# 17_-SP2_BUCKs_GPU_LOG_CPU-B.net
KiCad netlist of a schematic drawn in Altium Designer
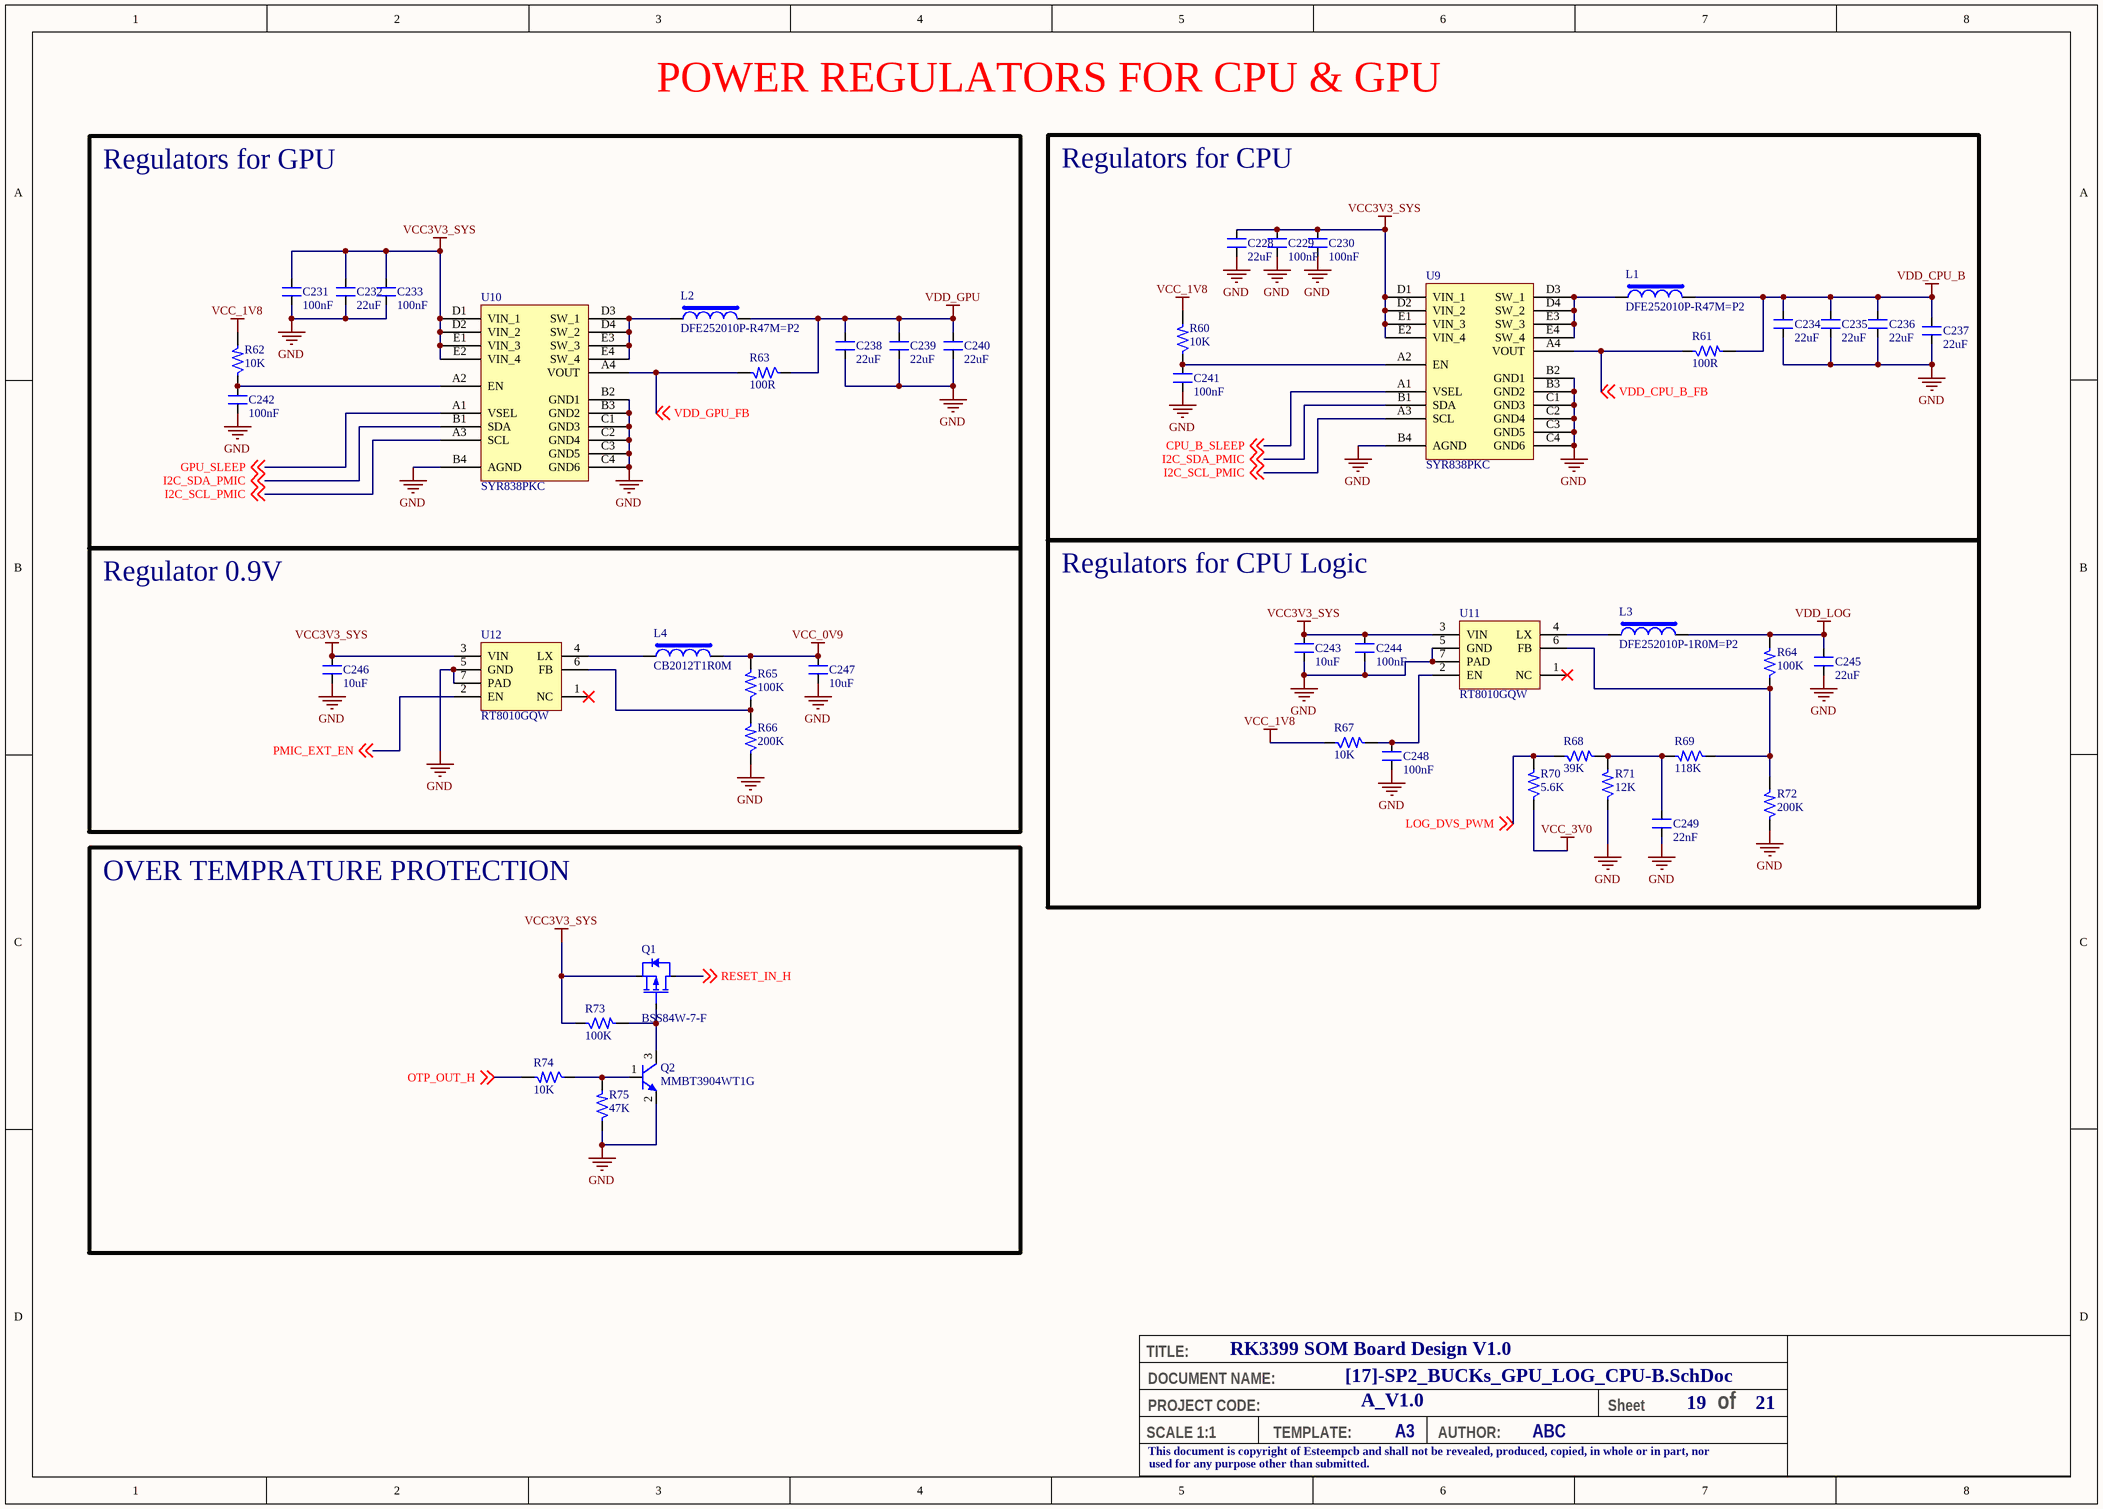
[diagram p0: [17]-SP2_BUCKs_GPU_LOG_CPU-B.SchDoc]

(export (version "E")
  (design (tool "Eeschema 10.0.6"))
  (components
    (comp (ref "C228")
      (value "22uF")
      (footprint "CAP_0603")
      (description "22µF ±20% 10V Ceramic Capacitor X5R 0603 (1608 Metric)")
      (fields
        (field (name "MANUFACTURER") "Murata Electronics")
        (field (name "MANUFACTURER PART NUMBER") "GRM188R61A226ME15D")
      )
      (libsource (lib "RK3399 _Module_Schlib") (part "CAP_22uF-10V-20%-0603"))
    )
    (comp (ref "C229")
      (value "100nF")
      (footprint "CAP_0402")
      (description "0.1µF ±10% 25V Ceramic Capacitor X7R 0402 (1005 Metric)")
      (fields
        (field (name "MANUFACTURER") "Walsin Technology Corporation")
        (field (name "MANUFACTURER PART NUMBER") "0402B104K250CT")
      )
      (libsource (lib "RK3399 _Module_Schlib") (part "CAP_100nF-25V-10%-0402"))
    )
    (comp (ref "C230")
      (value "100nF")
      (footprint "CAP_0402")
      (description "0.1µF ±10% 25V Ceramic Capacitor X7R 0402 (1005 Metric)")
      (fields
        (field (name "MANUFACTURER") "Walsin Technology Corporation")
        (field (name "MANUFACTURER PART NUMBER") "0402B104K250CT")
      )
      (libsource (lib "RK3399 _Module_Schlib") (part "CAP_100nF-25V-10%-0402"))
    )
    (comp (ref "C231")
      (value "100nF")
      (footprint "CAP_0402")
      (description "0.1µF ±10% 25V Ceramic Capacitor X7R 0402 (1005 Metric)")
      (fields
        (field (name "MANUFACTURER") "Walsin Technology Corporation")
        (field (name "MANUFACTURER PART NUMBER") "0402B104K250CT")
      )
      (libsource (lib "RK3399 _Module_Schlib") (part "CAP_100nF-25V-10%-0402"))
    )
    (comp (ref "C232")
      (value "22uF")
      (footprint "CAP_0603")
      (description "22µF ±20% 10V Ceramic Capacitor X5R 0603 (1608 Metric)")
      (fields
        (field (name "MANUFACTURER") "Murata Electronics")
        (field (name "MANUFACTURER PART NUMBER") "GRM188R61A226ME15D")
      )
      (libsource (lib "RK3399 _Module_Schlib") (part "CAP_22uF-10V-20%-0603"))
    )
    (comp (ref "C233")
      (value "100nF")
      (footprint "CAP_0402")
      (description "0.1µF ±10% 25V Ceramic Capacitor X7R 0402 (1005 Metric)")
      (fields
        (field (name "MANUFACTURER") "Walsin Technology Corporation")
        (field (name "MANUFACTURER PART NUMBER") "0402B104K250CT")
      )
      (libsource (lib "RK3399 _Module_Schlib") (part "CAP_100nF-25V-10%-0402"))
    )
    (comp (ref "C234")
      (value "22uF")
      (footprint "CAP_0603")
      (description "22µF ±20% 10V Ceramic Capacitor X5R 0603 (1608 Metric)")
      (fields
        (field (name "MANUFACTURER") "Murata Electronics")
        (field (name "MANUFACTURER PART NUMBER") "GRM188R61A226ME15D")
      )
      (libsource (lib "RK3399 _Module_Schlib") (part "CAP_22uF-10V-20%-0603"))
    )
    (comp (ref "C235")
      (value "22uF")
      (footprint "CAP_0603")
      (description "22µF ±20% 10V Ceramic Capacitor X5R 0603 (1608 Metric)")
      (fields
        (field (name "MANUFACTURER") "Murata Electronics")
        (field (name "MANUFACTURER PART NUMBER") "GRM188R61A226ME15D")
      )
      (libsource (lib "RK3399 _Module_Schlib") (part "CAP_22uF-10V-20%-0603"))
    )
    (comp (ref "C236")
      (value "22uF")
      (footprint "CAP_0603")
      (description "22µF ±20% 10V Ceramic Capacitor X5R 0603 (1608 Metric)")
      (fields
        (field (name "MANUFACTURER") "Murata Electronics")
        (field (name "MANUFACTURER PART NUMBER") "GRM188R61A226ME15D")
      )
      (libsource (lib "RK3399 _Module_Schlib") (part "CAP_22uF-10V-20%-0603"))
    )
    (comp (ref "C237")
      (value "22uF")
      (footprint "CAP_0603")
      (description "22µF ±20% 10V Ceramic Capacitor X5R 0603 (1608 Metric)")
      (fields
        (field (name "MANUFACTURER") "Murata Electronics")
        (field (name "MANUFACTURER PART NUMBER") "GRM188R61A226ME15D")
      )
      (libsource (lib "RK3399 _Module_Schlib") (part "CAP_22uF-10V-20%-0603"))
    )
    (comp (ref "C238")
      (value "22uF")
      (footprint "CAP_0603")
      (description "22µF ±20% 10V Ceramic Capacitor X5R 0603 (1608 Metric)")
      (fields
        (field (name "MANUFACTURER") "Murata Electronics")
        (field (name "MANUFACTURER PART NUMBER") "GRM188R61A226ME15D")
      )
      (libsource (lib "RK3399 _Module_Schlib") (part "CAP_22uF-10V-20%-0603"))
    )
    (comp (ref "C239")
      (value "22uF")
      (footprint "CAP_0603")
      (description "22µF ±20% 10V Ceramic Capacitor X5R 0603 (1608 Metric)")
      (fields
        (field (name "MANUFACTURER") "Murata Electronics")
        (field (name "MANUFACTURER PART NUMBER") "GRM188R61A226ME15D")
      )
      (libsource (lib "RK3399 _Module_Schlib") (part "CAP_22uF-10V-20%-0603"))
    )
    (comp (ref "C240")
      (value "22uF")
      (footprint "CAP_0603")
      (description "22µF ±20% 10V Ceramic Capacitor X5R 0603 (1608 Metric)")
      (fields
        (field (name "MANUFACTURER") "Murata Electronics")
        (field (name "MANUFACTURER PART NUMBER") "GRM188R61A226ME15D")
      )
      (libsource (lib "RK3399 _Module_Schlib") (part "CAP_22uF-10V-20%-0603"))
    )
    (comp (ref "C241")
      (value "100nF")
      (footprint "CAP_0402")
      (description "0.1µF ±10% 25V Ceramic Capacitor X7R 0402 (1005 Metric)")
      (fields
        (field (name "MANUFACTURER") "Walsin Technology Corporation")
        (field (name "MANUFACTURER PART NUMBER") "0402B104K250CT")
      )
      (libsource (lib "RK3399 _Module_Schlib") (part "CAP_100nF-25V-10%-0402"))
    )
    (comp (ref "C242")
      (value "100nF")
      (footprint "CAP_0402")
      (description "0.1µF ±10% 25V Ceramic Capacitor X7R 0402 (1005 Metric)")
      (fields
        (field (name "MANUFACTURER") "Walsin Technology Corporation")
        (field (name "MANUFACTURER PART NUMBER") "0402B104K250CT")
      )
      (libsource (lib "RK3399 _Module_Schlib") (part "CAP_100nF-25V-10%-0402"))
    )
    (comp (ref "C243")
      (value "10uF")
      (footprint "CAP_0402")
      (description "10µF ±20% 10V Ceramic Capacitor X5R 0402 (1005 Metric)")
      (fields
        (field (name "MANUFACTURER PART NUMBER") "CL05A106MP5NUNC")
        (field (name "MANUFACTURER") "Samsung Electro-Mechanics")
      )
      (libsource (lib "RK3399 _Module_Schlib") (part "CAP_10uF-10V-20%-0402"))
    )
    (comp (ref "C244")
      (value "100nF")
      (footprint "CAP_0402")
      (description "0.1µF ±10% 25V Ceramic Capacitor X7R 0402 (1005 Metric)")
      (fields
        (field (name "MANUFACTURER") "Walsin Technology Corporation")
        (field (name "MANUFACTURER PART NUMBER") "0402B104K250CT")
      )
      (libsource (lib "RK3399 _Module_Schlib") (part "CAP_100nF-25V-10%-0402"))
    )
    (comp (ref "C245")
      (value "22uF")
      (footprint "CAP_0603")
      (description "22µF ±20% 10V Ceramic Capacitor X5R 0603 (1608 Metric)")
      (fields
        (field (name "MANUFACTURER") "Murata Electronics")
        (field (name "MANUFACTURER PART NUMBER") "GRM188R61A226ME15D")
      )
      (libsource (lib "RK3399 _Module_Schlib") (part "CAP_22uF-10V-20%-0603"))
    )
    (comp (ref "C246")
      (value "10uF")
      (footprint "CAP_0402")
      (description "10µF ±20% 10V Ceramic Capacitor X5R 0402 (1005 Metric)")
      (fields
        (field (name "MANUFACTURER PART NUMBER") "CL05A106MP5NUNC")
        (field (name "MANUFACTURER") "Samsung Electro-Mechanics")
      )
      (libsource (lib "RK3399 _Module_Schlib") (part "CAP_10uF-10V-20%-0402"))
    )
    (comp (ref "C247")
      (value "10uF")
      (footprint "CAP_0402")
      (description "10µF ±20% 10V Ceramic Capacitor X5R 0402 (1005 Metric)")
      (fields
        (field (name "MANUFACTURER PART NUMBER") "CL05A106MP5NUNC")
        (field (name "MANUFACTURER") "Samsung Electro-Mechanics")
      )
      (libsource (lib "RK3399 _Module_Schlib") (part "CAP_10uF-10V-20%-0402"))
    )
    (comp (ref "C248")
      (value "100nF")
      (footprint "CAP_0402")
      (description "0.1µF ±10% 25V Ceramic Capacitor X7R 0402 (1005 Metric)")
      (fields
        (field (name "MANUFACTURER") "Walsin Technology Corporation")
        (field (name "MANUFACTURER PART NUMBER") "0402B104K250CT")
      )
      (libsource (lib "RK3399 _Module_Schlib") (part "CAP_100nF-25V-10%-0402"))
    )
    (comp (ref "C249")
      (value "22nF")
      (footprint "CAP_0402")
      (description "0.022µF ±10% 10V Ceramic Capacitor X7R 0402 (1005 Metric)")
      (fields
        (field (name "MANUFACTURER") "Samsung Electro-Mechanics")
        (field (name "MANUFACTURER PART NUMBER") "CL05B223KP5NNNC")
      )
      (libsource (lib "RK3399 _Module_Schlib") (part "CAP_22nF-10V-10%-0402"))
    )
    (comp (ref "L1")
      (value "DFE252010P-R47M=P2")
      (footprint "IND_1008")
      (description "470nH Shielded Wirewound Inductor 5A 35mOhm Max 1008 (2520 Metric)")
      (fields (field (name "MANUFACTURER") "Murata Electronics"))
      (libsource (lib "RK3399 _Module_Schlib") (part "IND_470nH-5A-20%-1008"))
    )
    (comp (ref "L2")
      (value "DFE252010P-R47M=P2")
      (footprint "IND_1008")
      (description "470nH Shielded Wirewound Inductor 5A 35mOhm Max 1008 (2520 Metric)")
      (fields (field (name "MANUFACTURER") "Murata Electronics"))
      (libsource (lib "RK3399 _Module_Schlib") (part "IND_470nH-5A-20%-1008"))
    )
    (comp (ref "L3")
      (value "DFE252010P-1R0M=P2")
      (footprint "IND_1008")
      (description "1µH Shielded Wirewound Inductor 3.8A 54mOhm Max 1008 (2520 Metric)")
      (fields (field (name "MANUFACTURER") "Murata Electronics"))
      (libsource (lib "RK3399 _Module_Schlib") (part "IND_1uH-3.8A-20%-1008"))
    )
    (comp (ref "L4")
      (value "CB2012T1R0M")
      (footprint "IND_0805")
      (description "1uH ±20% 500mA 150mΩ 0805 Inductors (SMD) RoHS")
      (fields (field (name "MANUFACTURER") "Taiyo Yuden"))
      (libsource (lib "RK3399 _Module_Schlib") (part "IND_1uF-0.5A-20%-0805"))
    )
    (comp (ref "Q1")
      (value "BSS84W-7-F")
      (footprint "SOT-323-3")
      (description "P-Channel 50V 130mA (Ta) 200mW (Ta) Surface Mount SOT-323")
      (fields (field (name "MANUFACTURER") "Diodes Incorporated"))
      (libsource (lib "RK3399 _Module_Schlib") (part "MOSFET-P_50V-130mA-SOT-323"))
    )
    (comp (ref "Q2")
      (value "MMBT3904WT1G")
      (footprint "SOT-323-3")
      (description "Bipolar Transistors - BJT 200mA 60V NPN")
      (fields (field (name "MANUFACTURER") "ON Semiconductor"))
      (libsource (lib "RK3399 _Module_Schlib") (part "TRNS-NPN_60V-0.2A-SOT323"))
    )
    (comp (ref "R60")
      (value "10K")
      (footprint "RES_0402")
      (description "10 kOhms ±1% 0.1W, 1/10W Chip Resistor 0402 (1005 Metric) Anti-Sulfur Thin Film")
      (fields
        (field (name "MANUFACTURER") "Vishay Beyschlag/Draloric/BC Components")
        (field (name "MANUFACTURER PART NUMBER") "MCS04020C1002FE000")
      )
      (libsource (lib "RK3399 _Module_Schlib") (part "RES_10K-0.1W-1%-0402"))
    )
    (comp (ref "R61")
      (value "100R")
      (footprint "RES_0402")
      (fields
        (field (name "MANUFACTURER") "KOA Speer Electronics, Inc.")
        (field (name "MANUFACTURER PART NUMBER") "RK73H1ETTP1000F")
      )
      (libsource (lib "RK3399 _Module_Schlib") (part "RES_100R-0.1W-1%-0402"))
    )
    (comp (ref "R62")
      (value "10K")
      (footprint "RES_0402")
      (description "10 kOhms ±1% 0.1W, 1/10W Chip Resistor 0402 (1005 Metric) Anti-Sulfur Thin Film")
      (fields
        (field (name "MANUFACTURER") "Vishay Beyschlag/Draloric/BC Components")
        (field (name "MANUFACTURER PART NUMBER") "MCS04020C1002FE000")
      )
      (libsource (lib "RK3399 _Module_Schlib") (part "RES_10K-0.1W-1%-0402"))
    )
    (comp (ref "R63")
      (value "100R")
      (footprint "RES_0402")
      (fields
        (field (name "MANUFACTURER") "KOA Speer Electronics, Inc.")
        (field (name "MANUFACTURER PART NUMBER") "RK73H1ETTP1000F")
      )
      (libsource (lib "RK3399 _Module_Schlib") (part "RES_100R-0.1W-1%-0402"))
    )
    (comp (ref "R64")
      (value "100K")
      (footprint "RES_0402")
      (description "100 kOhms ±1% 0.1W, 1/10W Chip Resistor 0402 (1005 Metric) Anti-Sulfur Thin Film")
      (fields
        (field (name "MANUFACTURER") "Vishay Beyschlag/Draloric/BC Components")
        (field (name "MANUFACTURER PART NUMBER") "MCS04020C1003FE000")
      )
      (libsource (lib "RK3399 _Module_Schlib") (part "RES_100K-0.1W-1%-0402"))
    )
    (comp (ref "R65")
      (value "100K")
      (footprint "RES_0402")
      (description "100 kOhms ±1% 0.1W, 1/10W Chip Resistor 0402 (1005 Metric) Anti-Sulfur Thin Film")
      (fields
        (field (name "MANUFACTURER") "Vishay Beyschlag/Draloric/BC Components")
        (field (name "MANUFACTURER PART NUMBER") "MCS04020C1003FE000")
      )
      (libsource (lib "RK3399 _Module_Schlib") (part "RES_100K-0.1W-1%-0402"))
    )
    (comp (ref "R66")
      (value "200K")
      (footprint "RES_0402")
      (description "200 kOhms ±1% 0.1W, 1/10W Chip Resistor 0402 (1005 Metric) Automotive AEC-Q200 Thick Film")
      (fields
        (field (name "MANUFACTURER") "Panasonic Electronic Components")
        (field (name "MANUFACTURER PART NUMBER") "ERJ-2RKF2003X")
      )
      (libsource (lib "RK3399 _Module_Schlib") (part "RES_200K-0.1W-1%-0402"))
    )
    (comp (ref "R67")
      (value "10K")
      (footprint "RES_0402")
      (description "10 kOhms ±1% 0.1W, 1/10W Chip Resistor 0402 (1005 Metric) Anti-Sulfur Thin Film")
      (fields
        (field (name "MANUFACTURER") "Vishay Beyschlag/Draloric/BC Components")
        (field (name "MANUFACTURER PART NUMBER") "MCS04020C1002FE000")
      )
      (libsource (lib "RK3399 _Module_Schlib") (part "RES_10K-0.1W-1%-0402"))
    )
    (comp (ref "R68")
      (value "39K")
      (footprint "RES_0402")
      (fields
        (field (name "MANUFACTURER") "KOA Speer Electronics, Inc.")
        (field (name "MANUFACTURER PART NUMBER") "RK73H1ETTP3902F")
      )
      (libsource (lib "RK3399 _Module_Schlib") (part "RES_39K-0.1W-1%-0402"))
    )
    (comp (ref "R69")
      (value "118K")
      (footprint "RES_0402")
      (fields
        (field (name "MANUFACTURER") "KOA Speer Electronics, Inc.")
        (field (name "MANUAFCTURER PART NUMBER") "RK73H1ETTP1183F")
      )
      (libsource (lib "RK3399 _Module_Schlib") (part "RES_118K-0.1W-1%-0402"))
    )
    (comp (ref "R70")
      (value "5.6K")
      (footprint "RES_0402")
      (fields
        (field (name "MANUFACTURER") "KOA Speer Electronics, Inc.")
        (field (name "MANUFACTURER PART NUMBER") "RK73H1ETTP5601F")
      )
      (libsource (lib "RK3399 _Module_Schlib") (part "RES_5.6K-0.1W-1%-0402"))
    )
    (comp (ref "R71")
      (value "12K")
      (footprint "RES_0402")
      (description "12 kOhms ±1% 0.1W, 1/10W Chip Resistor 0402 (1005 Metric) Anti-Sulfur Thin Film")
      (fields
        (field (name "MANUFACTURER") "Vishay Beyschlag/Draloric/BC Components")
        (field (name "MANUFACTURER PART NUMBER") "MCS04020C1202FE000")
      )
      (libsource (lib "RK3399 _Module_Schlib") (part "RES_12K-0.1W-1%-0402"))
    )
    (comp (ref "R72")
      (value "200K")
      (footprint "RES_0402")
      (description "200 kOhms ±1% 0.1W, 1/10W Chip Resistor 0402 (1005 Metric) Automotive AEC-Q200 Thick Film")
      (fields
        (field (name "MANUFACTURER") "Panasonic Electronic Components")
        (field (name "MANUFACTURER PART NUMBER") "ERJ-2RKF2003X")
      )
      (libsource (lib "RK3399 _Module_Schlib") (part "RES_200K-0.1W-1%-0402"))
    )
    (comp (ref "R73")
      (value "100K")
      (footprint "RES_0402")
      (description "100 kOhms ±1% 0.1W, 1/10W Chip Resistor 0402 (1005 Metric) Anti-Sulfur Thin Film")
      (fields
        (field (name "MANUFACTURER") "Vishay Beyschlag/Draloric/BC Components")
        (field (name "MANUFACTURER PART NUMBER") "MCS04020C1003FE000")
      )
      (libsource (lib "RK3399 _Module_Schlib") (part "RES_100K-0.1W-1%-0402"))
    )
    (comp (ref "R74")
      (value "10K")
      (footprint "RES_0402")
      (description "10 kOhms ±1% 0.1W, 1/10W Chip Resistor 0402 (1005 Metric) Anti-Sulfur Thin Film")
      (fields
        (field (name "MANUFACTURER") "Vishay Beyschlag/Draloric/BC Components")
        (field (name "MANUFACTURER PART NUMBER") "MCS04020C1002FE000")
      )
      (libsource (lib "RK3399 _Module_Schlib") (part "RES_10K-0.1W-1%-0402"))
    )
    (comp (ref "R75")
      (value "47K")
      (footprint "RES_0402")
      (description "47 kOhms ±1% 0.1W, 1/10W Chip Resistor 0402 (1005 Metric) Automotive AEC-Q200 Thick Film")
      (fields
        (field (name "MANUFACTURER") "Panasonic Electronic Components")
        (field (name "MANUFACTURER PART NUMBER") "ERJ-2RKF4702X")
      )
      (libsource (lib "RK3399 _Module_Schlib") (part "RES_47K-0.1W-1%-0402"))
    )
    (comp (ref "U9")
      (value "SYR838PKC")
      (footprint "CSP20_15.7_100x84_SMD")
      (description "Step-Down Positive Programmable 1 6A 2.4MHz CSP1.56*1.96-20 DC-DC Converters RoHS")
      (fields (field (name "MANUFACTURER") "Silergy Corp"))
      (libsource (lib "RK3399 _Module_Schlib") (part "IC_SYR838PKC"))
    )
    (comp (ref "U10")
      (value "SYR838PKC")
      (footprint "CSP20_15.7_100x84_SMD")
      (description "Step-Down Positive Programmable 1 6A 2.4MHz CSP1.56*1.96-20 DC-DC Converters RoHS")
      (fields (field (name "MANUFACTURER") "Silergy Corp"))
      (libsource (lib "RK3399 _Module_Schlib") (part "IC_SYR838PKC"))
    )
    (comp (ref "U11")
      (value "RT8010GQW")
      (footprint "WDFN-6_26_133X100_SMD")
      (description "Buck Switching Regulator IC Positive Adjustable 0.6V 1 Output 1A 6-WDFN Exposed Pad")
      (fields (field (name "MANUFACTURER") "Richtek USA Inc."))
      (libsource (lib "RK3399 _Module_Schlib") (part "REG-ADJ_5.5V-5.5V-1A-6-WDFN"))
    )
    (comp (ref "U12")
      (value "RT8010GQW")
      (footprint "WDFN-6_26_133X100_SMD")
      (description "Buck Switching Regulator IC Positive Adjustable 0.6V 1 Output 1A 6-WDFN Exposed Pad")
      (fields (field (name "MANUFACTURER") "Richtek USA Inc."))
      (libsource (lib "RK3399 _Module_Schlib") (part "REG-ADJ_5.5V-5.5V-1A-6-WDFN"))
    )
  )
  (nets
    (net (code "1") (name "CPU_B_SLEEP") (class "Default")
      (node (ref "U9") (pin "A1") (pinfunction "VSEL_A1") (pintype "passive"))
    )
    (net (code "2") (name "GND") (class "Default")
      (node (ref "C228") (pin "1") (pinfunction "1_1") (pintype "passive"))
      (node (ref "C229") (pin "1") (pinfunction "1_1") (pintype "passive"))
      (node (ref "C230") (pin "1") (pinfunction "1_1") (pintype "passive"))
      (node (ref "C231") (pin "1") (pinfunction "1_1") (pintype "passive"))
      (node (ref "C232") (pin "1") (pinfunction "1_1") (pintype "passive"))
      (node (ref "C233") (pin "1") (pinfunction "1_1") (pintype "passive"))
      (node (ref "C234") (pin "1") (pinfunction "1_1") (pintype "passive"))
      (node (ref "C235") (pin "1") (pinfunction "1_1") (pintype "passive"))
      (node (ref "C236") (pin "1") (pinfunction "1_1") (pintype "passive"))
      (node (ref "C237") (pin "1") (pinfunction "1_1") (pintype "passive"))
      (node (ref "C238") (pin "1") (pinfunction "1_1") (pintype "passive"))
      (node (ref "C239") (pin "1") (pinfunction "1_1") (pintype "passive"))
      (node (ref "C240") (pin "1") (pinfunction "1_1") (pintype "passive"))
      (node (ref "C241") (pin "1") (pinfunction "1_1") (pintype "passive"))
      (node (ref "C242") (pin "1") (pinfunction "1_1") (pintype "passive"))
      (node (ref "C243") (pin "1") (pinfunction "1_1") (pintype "passive"))
      (node (ref "C244") (pin "1") (pinfunction "1_1") (pintype "passive"))
      (node (ref "C245") (pin "1") (pinfunction "1_1") (pintype "passive"))
      (node (ref "C246") (pin "1") (pinfunction "1_1") (pintype "passive"))
      (node (ref "C247") (pin "1") (pinfunction "1_1") (pintype "passive"))
      (node (ref "C248") (pin "1") (pinfunction "1_1") (pintype "passive"))
      (node (ref "C249") (pin "1") (pinfunction "1_1") (pintype "passive"))
      (node (ref "Q2") (pin "2") (pinfunction "E_2") (pintype "passive"))
      (node (ref "R66") (pin "1") (pinfunction "1_1") (pintype "passive"))
      (node (ref "R71") (pin "1") (pinfunction "1_1") (pintype "passive"))
      (node (ref "R72") (pin "1") (pinfunction "1_1") (pintype "passive"))
      (node (ref "R75") (pin "1") (pinfunction "1_1") (pintype "passive"))
      (node (ref "U10") (pin "B2") (pinfunction "GND1_B2") (pintype "passive"))
      (node (ref "U10") (pin "B3") (pinfunction "GND2_B3") (pintype "passive"))
      (node (ref "U10") (pin "B4") (pinfunction "AGND_B4") (pintype "passive"))
      (node (ref "U10") (pin "C1") (pinfunction "GND3_C1") (pintype "passive"))
      (node (ref "U10") (pin "C2") (pinfunction "GND4_C2") (pintype "passive"))
      (node (ref "U10") (pin "C3") (pinfunction "GND5_C3") (pintype "passive"))
      (node (ref "U10") (pin "C4") (pinfunction "GND6_C4") (pintype "passive"))
      (node (ref "U11") (pin "5") (pinfunction "GND_5") (pintype "passive"))
      (node (ref "U11") (pin "7") (pinfunction "PAD_7") (pintype "passive"))
      (node (ref "U12") (pin "5") (pinfunction "GND_5") (pintype "passive"))
      (node (ref "U12") (pin "7") (pinfunction "PAD_7") (pintype "passive"))
      (node (ref "U9") (pin "B2") (pinfunction "GND1_B2") (pintype "passive"))
      (node (ref "U9") (pin "B3") (pinfunction "GND2_B3") (pintype "passive"))
      (node (ref "U9") (pin "B4") (pinfunction "AGND_B4") (pintype "passive"))
      (node (ref "U9") (pin "C1") (pinfunction "GND3_C1") (pintype "passive"))
      (node (ref "U9") (pin "C2") (pinfunction "GND4_C2") (pintype "passive"))
      (node (ref "U9") (pin "C3") (pinfunction "GND5_C3") (pintype "passive"))
      (node (ref "U9") (pin "C4") (pinfunction "GND6_C4") (pintype "passive"))
    )
    (net (code "3") (name "GPU_SLEEP") (class "Default")
      (node (ref "U10") (pin "A1") (pinfunction "VSEL_A1") (pintype "passive"))
    )
    (net (code "4") (name "I2C_SCL_PMIC") (class "Default")
      (node (ref "U10") (pin "A3") (pinfunction "SCL_A3") (pintype "passive"))
      (node (ref "U9") (pin "A3") (pinfunction "SCL_A3") (pintype "passive"))
    )
    (net (code "5") (name "I2C_SDA_PMIC") (class "Default")
      (node (ref "U10") (pin "B1") (pinfunction "SDA_B1") (pintype "passive"))
      (node (ref "U9") (pin "B1") (pinfunction "SDA_B1") (pintype "passive"))
    )
    (net (code "6") (name "LOG_DVS_PWM") (class "Default")
      (node (ref "R68") (pin "1") (pinfunction "1_1") (pintype "passive"))
      (node (ref "R70") (pin "2") (pinfunction "2_2") (pintype "passive"))
    )
    (net (code "7") (name "Net-(C249-Pad2)") (class "Default")
      (node (ref "C249") (pin "2") (pinfunction "2_2") (pintype "passive"))
      (node (ref "R68") (pin "2") (pinfunction "2_2") (pintype "passive"))
      (node (ref "R69") (pin "2") (pinfunction "2_2") (pintype "passive"))
      (node (ref "R71") (pin "2") (pinfunction "2_2") (pintype "passive"))
    )
    (net (code "8") (name "Net-(Q1-G)") (class "Default")
      (node (ref "Q1") (pin "1") (pinfunction "G_1") (pintype "passive"))
      (node (ref "Q2") (pin "3") (pinfunction "C_3") (pintype "passive"))
      (node (ref "R73") (pin "2") (pinfunction "2_2") (pintype "passive"))
    )
    (net (code "9") (name "Net-(Q2-B)") (class "Default")
      (node (ref "Q2") (pin "1") (pinfunction "B_1") (pintype "passive"))
      (node (ref "R74") (pin "1") (pinfunction "1_1") (pintype "passive"))
      (node (ref "R75") (pin "2") (pinfunction "2_2") (pintype "passive"))
    )
    (net (code "10") (name "Net-(U9-EN)") (class "Default")
      (node (ref "C241") (pin "2") (pinfunction "2_2") (pintype "passive"))
      (node (ref "R60") (pin "1") (pinfunction "1_1") (pintype "passive"))
      (node (ref "U9") (pin "A2") (pinfunction "EN_A2") (pintype "passive"))
    )
    (net (code "11") (name "Net-(U9-SW_1)") (class "Default")
      (node (ref "L1") (pin "1") (pinfunction "1_1") (pintype "passive"))
      (node (ref "U9") (pin "D3") (pinfunction "SW_1_D3") (pintype "passive"))
      (node (ref "U9") (pin "D4") (pinfunction "SW_2_D4") (pintype "passive"))
      (node (ref "U9") (pin "E3") (pinfunction "SW_3_E3") (pintype "passive"))
      (node (ref "U9") (pin "E4") (pinfunction "SW_4_E4") (pintype "passive"))
    )
    (net (code "12") (name "Net-(U10-EN)") (class "Default")
      (node (ref "C242") (pin "2") (pinfunction "2_2") (pintype "passive"))
      (node (ref "R62") (pin "1") (pinfunction "1_1") (pintype "passive"))
      (node (ref "U10") (pin "A2") (pinfunction "EN_A2") (pintype "passive"))
    )
    (net (code "13") (name "Net-(U10-SW_1)") (class "Default")
      (node (ref "L2") (pin "1") (pinfunction "1_1") (pintype "passive"))
      (node (ref "U10") (pin "D3") (pinfunction "SW_1_D3") (pintype "passive"))
      (node (ref "U10") (pin "D4") (pinfunction "SW_2_D4") (pintype "passive"))
      (node (ref "U10") (pin "E3") (pinfunction "SW_3_E3") (pintype "passive"))
      (node (ref "U10") (pin "E4") (pinfunction "SW_4_E4") (pintype "passive"))
    )
    (net (code "14") (name "Net-(U11-EN)") (class "Default")
      (node (ref "C248") (pin "2") (pinfunction "2_2") (pintype "passive"))
      (node (ref "R67") (pin "2") (pinfunction "2_2") (pintype "passive"))
      (node (ref "U11") (pin "2") (pinfunction "EN_2") (pintype "passive"))
    )
    (net (code "15") (name "Net-(U11-FB)") (class "Default")
      (node (ref "R64") (pin "1") (pinfunction "1_1") (pintype "passive"))
      (node (ref "R69") (pin "1") (pinfunction "1_1") (pintype "passive"))
      (node (ref "R72") (pin "2") (pinfunction "2_2") (pintype "passive"))
      (node (ref "U11") (pin "6") (pinfunction "FB_6") (pintype "passive"))
    )
    (net (code "16") (name "Net-(U11-LX)") (class "Default")
      (node (ref "L3") (pin "1") (pinfunction "1_1") (pintype "passive"))
      (node (ref "U11") (pin "4") (pinfunction "LX_4") (pintype "passive"))
    )
    (net (code "17") (name "Net-(U12-FB)") (class "Default")
      (node (ref "R65") (pin "1") (pinfunction "1_1") (pintype "passive"))
      (node (ref "R66") (pin "2") (pinfunction "2_2") (pintype "passive"))
      (node (ref "U12") (pin "6") (pinfunction "FB_6") (pintype "passive"))
    )
    (net (code "18") (name "Net-(U12-LX)") (class "Default")
      (node (ref "L4") (pin "1") (pinfunction "1_1") (pintype "passive"))
      (node (ref "U12") (pin "4") (pinfunction "LX_4") (pintype "passive"))
    )
    (net (code "19") (name "OTP_OUT_H") (class "Default")
      (node (ref "R74") (pin "2") (pinfunction "2_2") (pintype "passive"))
    )
    (net (code "20") (name "PMIC_EXT_EN") (class "Default")
      (node (ref "U12") (pin "2") (pinfunction "EN_2") (pintype "passive"))
    )
    (net (code "21") (name "RESET_IN_H") (class "Default")
      (node (ref "Q1") (pin "3") (pinfunction "D_3") (pintype "passive"))
    )
    (net (code "22") (name "VCC3V3_SYS") (class "Default")
      (node (ref "C228") (pin "2") (pinfunction "2_2") (pintype "passive"))
      (node (ref "C229") (pin "2") (pinfunction "2_2") (pintype "passive"))
      (node (ref "C230") (pin "2") (pinfunction "2_2") (pintype "passive"))
      (node (ref "C231") (pin "2") (pinfunction "2_2") (pintype "passive"))
      (node (ref "C232") (pin "2") (pinfunction "2_2") (pintype "passive"))
      (node (ref "C233") (pin "2") (pinfunction "2_2") (pintype "passive"))
      (node (ref "C243") (pin "2") (pinfunction "2_2") (pintype "passive"))
      (node (ref "C244") (pin "2") (pinfunction "2_2") (pintype "passive"))
      (node (ref "C246") (pin "2") (pinfunction "2_2") (pintype "passive"))
      (node (ref "Q1") (pin "2") (pinfunction "S_2") (pintype "passive"))
      (node (ref "R73") (pin "1") (pinfunction "1_1") (pintype "passive"))
      (node (ref "U10") (pin "D1") (pinfunction "VIN_1_D1") (pintype "passive"))
      (node (ref "U10") (pin "D2") (pinfunction "VIN_2_D2") (pintype "passive"))
      (node (ref "U10") (pin "E1") (pinfunction "VIN_3_E1") (pintype "passive"))
      (node (ref "U10") (pin "E2") (pinfunction "VIN_4_E2") (pintype "passive"))
      (node (ref "U11") (pin "3") (pinfunction "VIN_3") (pintype "passive"))
      (node (ref "U12") (pin "3") (pinfunction "VIN_3") (pintype "passive"))
      (node (ref "U9") (pin "D1") (pinfunction "VIN_1_D1") (pintype "passive"))
      (node (ref "U9") (pin "D2") (pinfunction "VIN_2_D2") (pintype "passive"))
      (node (ref "U9") (pin "E1") (pinfunction "VIN_3_E1") (pintype "passive"))
      (node (ref "U9") (pin "E2") (pinfunction "VIN_4_E2") (pintype "passive"))
    )
    (net (code "23") (name "VCC_0V9") (class "Default")
      (node (ref "C247") (pin "2") (pinfunction "2_2") (pintype "passive"))
      (node (ref "L4") (pin "2") (pinfunction "2_2") (pintype "passive"))
      (node (ref "R65") (pin "2") (pinfunction "2_2") (pintype "passive"))
    )
    (net (code "24") (name "VCC_1V8") (class "Default")
      (node (ref "R60") (pin "2") (pinfunction "2_2") (pintype "passive"))
      (node (ref "R62") (pin "2") (pinfunction "2_2") (pintype "passive"))
      (node (ref "R67") (pin "1") (pinfunction "1_1") (pintype "passive"))
    )
    (net (code "25") (name "VCC_3V0") (class "Default")
      (node (ref "R70") (pin "1") (pinfunction "1_1") (pintype "passive"))
    )
    (net (code "26") (name "VDD_CPU_B") (class "Default")
      (node (ref "C234") (pin "2") (pinfunction "2_2") (pintype "passive"))
      (node (ref "C235") (pin "2") (pinfunction "2_2") (pintype "passive"))
      (node (ref "C236") (pin "2") (pinfunction "2_2") (pintype "passive"))
      (node (ref "C237") (pin "2") (pinfunction "2_2") (pintype "passive"))
      (node (ref "L1") (pin "2") (pinfunction "2_2") (pintype "passive"))
      (node (ref "R61") (pin "2") (pinfunction "2_2") (pintype "passive"))
    )
    (net (code "27") (name "VDD_CPU_B_FB") (class "Default")
      (node (ref "R61") (pin "1") (pinfunction "1_1") (pintype "passive"))
      (node (ref "U9") (pin "A4") (pinfunction "VOUT_A4") (pintype "passive"))
    )
    (net (code "28") (name "VDD_GPU") (class "Default")
      (node (ref "C238") (pin "2") (pinfunction "2_2") (pintype "passive"))
      (node (ref "C239") (pin "2") (pinfunction "2_2") (pintype "passive"))
      (node (ref "C240") (pin "2") (pinfunction "2_2") (pintype "passive"))
      (node (ref "L2") (pin "2") (pinfunction "2_2") (pintype "passive"))
      (node (ref "R63") (pin "1") (pinfunction "1_1") (pintype "passive"))
    )
    (net (code "29") (name "VDD_GPU_FB") (class "Default")
      (node (ref "R63") (pin "2") (pinfunction "2_2") (pintype "passive"))
      (node (ref "U10") (pin "A4") (pinfunction "VOUT_A4") (pintype "passive"))
    )
    (net (code "30") (name "VDD_LOG") (class "Default")
      (node (ref "C245") (pin "2") (pinfunction "2_2") (pintype "passive"))
      (node (ref "L3") (pin "2") (pinfunction "2_2") (pintype "passive"))
      (node (ref "R64") (pin "2") (pinfunction "2_2") (pintype "passive"))
    )
    (net (code "31") (name "unconnected-(U11-NC-Pad1)") (class "Default")
      (node (ref "U11") (pin "1") (pinfunction "NC_1") (pintype "passive+no_connect"))
    )
    (net (code "32") (name "unconnected-(U12-NC-Pad1)") (class "Default")
      (node (ref "U12") (pin "1") (pinfunction "NC_1") (pintype "passive+no_connect"))
    )
  )
)
